# internal_env_board_with_LCD.net
KiCad netlist of a schematic drawn in EAGLE
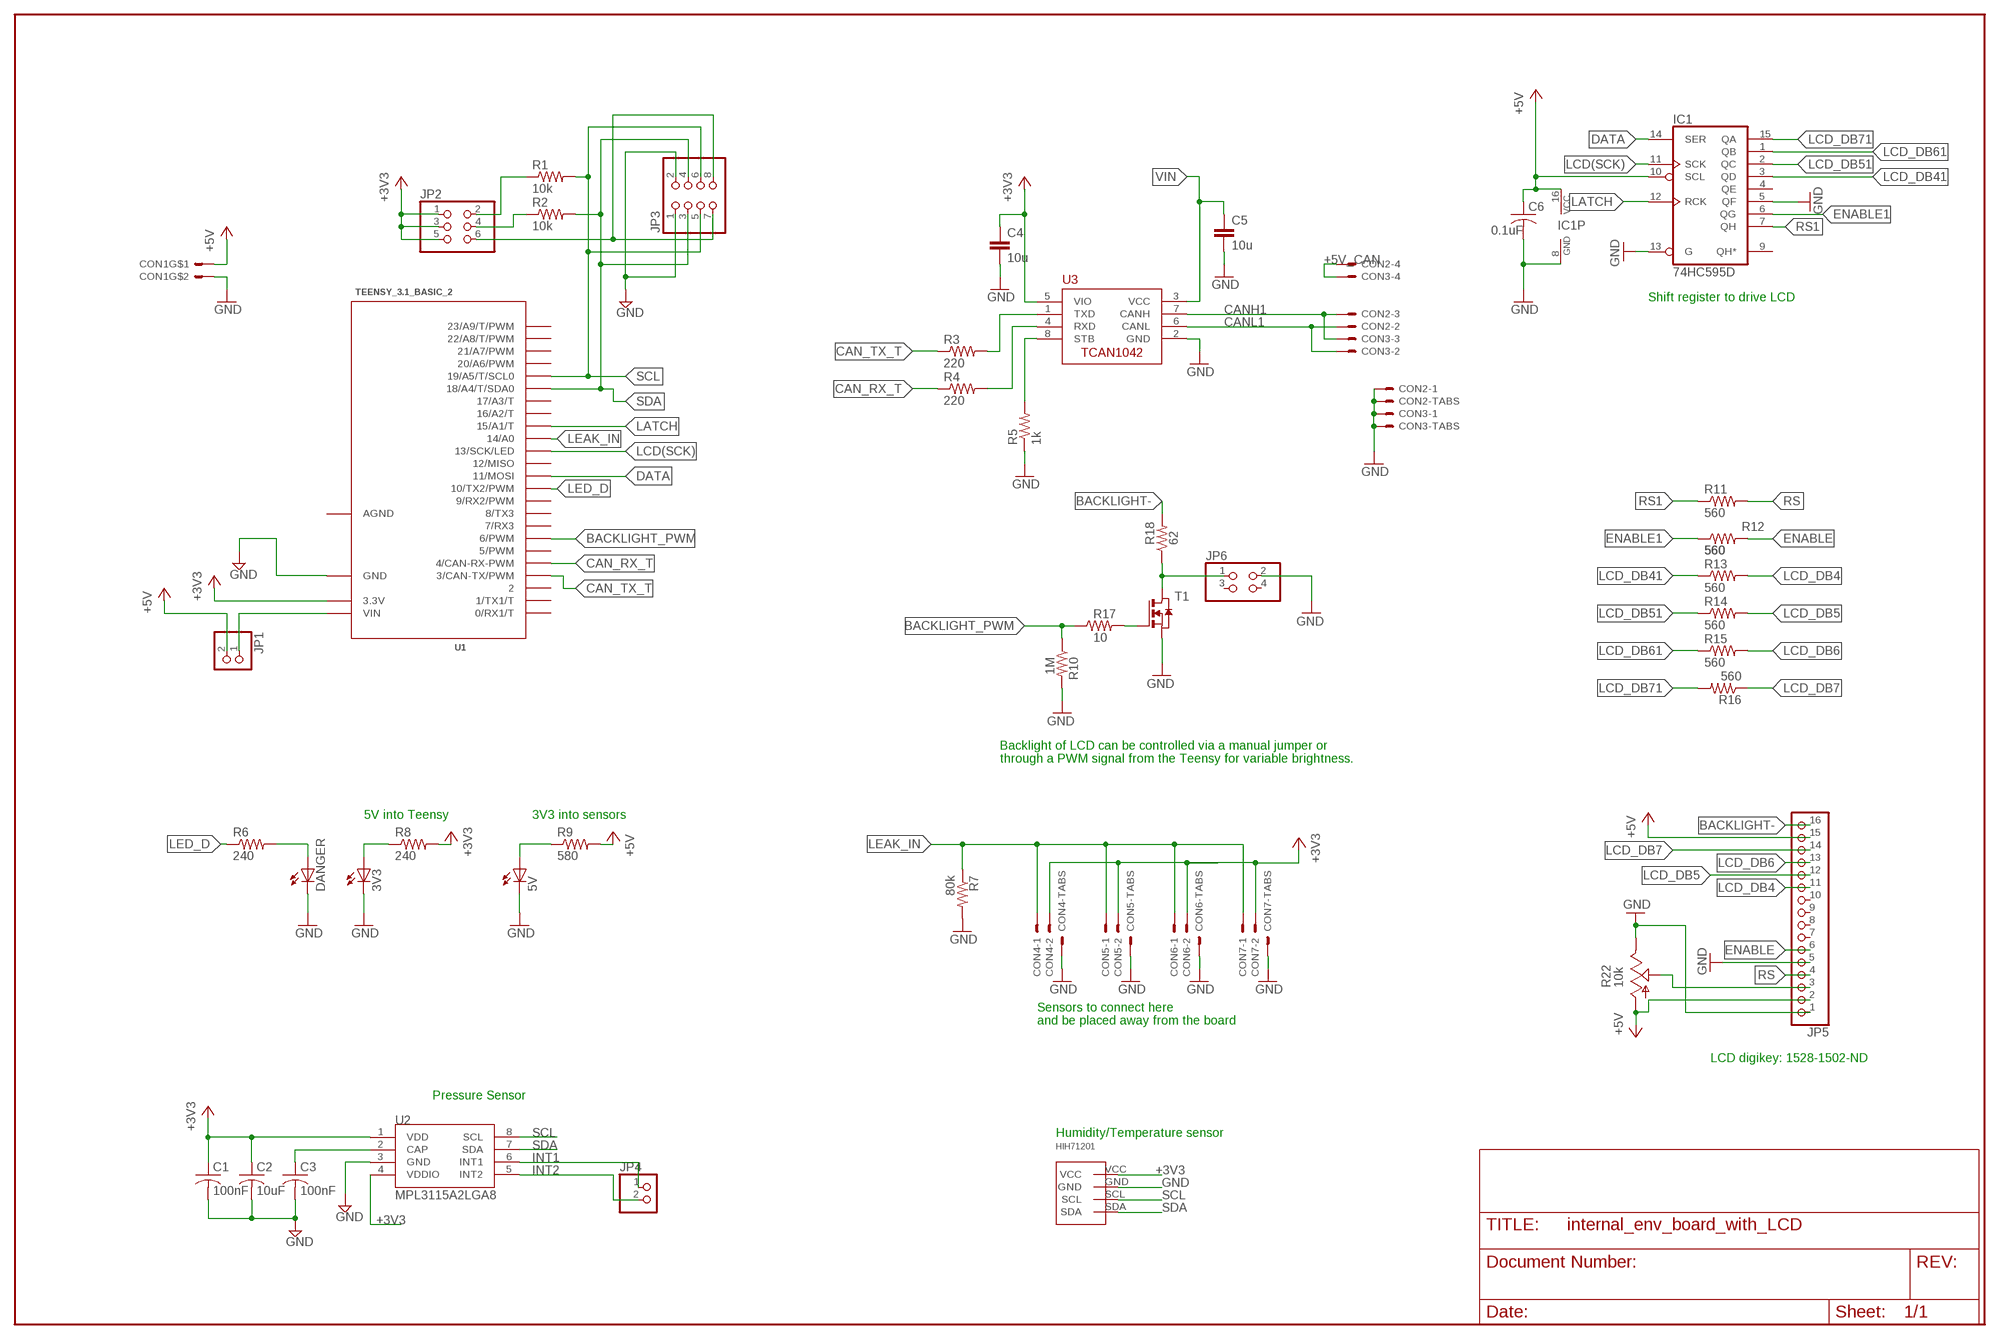
[diagram p0: schematic, sheet 1]

(export (version "E")
  (design (tool "Eeschema 10.0.6"))
  (components
    (comp (ref "3V3")
      (value "LEDSMT1206")
      (footprint "eagle-import:1206")
      (libsource (lib "eagle-import") (part "LEDSMT1206"))
    )
    (comp (ref "5V")
      (value "LEDSMT1206")
      (footprint "eagle-import:1206")
      (libsource (lib "eagle-import") (part "LEDSMT1206"))
    )
    (comp (ref "C1")
      (value "100nF")
      (footprint "eagle-import:C1206")
      (libsource (lib "eagle-import") (part "C-USC1206"))
    )
    (comp (ref "C2")
      (value "10uF")
      (footprint "eagle-import:C1206")
      (libsource (lib "eagle-import") (part "C-USC1206"))
    )
    (comp (ref "C3")
      (value "100nF")
      (footprint "eagle-import:C1206")
      (libsource (lib "eagle-import") (part "C-USC1206"))
    )
    (comp (ref "C4")
      (value "10u")
      (footprint "eagle-import:C0805")
      (libsource (lib "eagle-import") (part "C-EUC0805"))
    )
    (comp (ref "C5")
      (value "10u")
      (footprint "eagle-import:C0805")
      (libsource (lib "eagle-import") (part "C-EUC0805"))
    )
    (comp (ref "C6")
      (value "0.1uF")
      (footprint "eagle-import:C2012")
      (libsource (lib "eagle-import") (part "resistor_C-USC2012"))
    )
    (comp (ref "CON1")
      (value "MOLEX_5566-2")
      (footprint "eagle-import:5566-2")
      (libsource (lib "eagle-import") (part "MOLEX_5566-2"))
    )
    (comp (ref "CON2")
      (value "SM04B-GHS-TB")
      (footprint "eagle-import:SM04B-GHS-TB")
      (libsource (lib "eagle-import") (part "SM04B-GHS-TB"))
    )
    (comp (ref "CON3")
      (value "SM04B-GHS-TB")
      (footprint "eagle-import:SM04B-GHS-TB")
      (libsource (lib "eagle-import") (part "SM04B-GHS-TB"))
    )
    (comp (ref "CON4")
      (value "SM02B-GHS-TB")
      (footprint "eagle-import:SM02B-GHS-TB")
      (libsource (lib "eagle-import") (part "SM02B-GHS-TB"))
    )
    (comp (ref "CON5")
      (value "SM02B-GHS-TB")
      (footprint "eagle-import:SM02B-GHS-TB")
      (libsource (lib "eagle-import") (part "SM02B-GHS-TB"))
    )
    (comp (ref "CON6")
      (value "SM02B-GHS-TB")
      (footprint "eagle-import:SM02B-GHS-TB")
      (libsource (lib "eagle-import") (part "SM02B-GHS-TB"))
    )
    (comp (ref "CON7")
      (value "SM02B-GHS-TB")
      (footprint "eagle-import:SM02B-GHS-TB")
      (libsource (lib "eagle-import") (part "SM02B-GHS-TB"))
    )
    (comp (ref "DANGER")
      (value "LEDSMT1206")
      (footprint "eagle-import:1206")
      (libsource (lib "eagle-import") (part "LEDSMT1206"))
    )
    (comp (ref "HIH71201")
      (value "HIH7120")
      (footprint "eagle-import:SIP4")
      (libsource (lib "eagle-import") (part "HIH7120"))
    )
    (comp (ref "IC1")
      (value "74HC595D")
      (footprint "eagle-import:SO16")
      (libsource (lib "eagle-import") (part "74595DHC"))
    )
    (comp (ref "JP1")
      (value "PINHD-1X2")
      (footprint "eagle-import:1X02")
      (libsource (lib "eagle-import") (part "pinhead_325_PINHD-1X2"))
    )
    (comp (ref "JP2")
      (value "PINHD-2X3")
      (footprint "eagle-import:2X03")
      (libsource (lib "eagle-import") (part "PINHD-2X3"))
    )
    (comp (ref "JP3")
      (value "PINHD-2X4")
      (footprint "eagle-import:2X04")
      (libsource (lib "eagle-import") (part "PINHD-2X4"))
    )
    (comp (ref "JP4")
      (value "PINHD-1X2")
      (footprint "eagle-import:1X02")
      (libsource (lib "eagle-import") (part "PINHD-1X2"))
    )
    (comp (ref "JP5")
      (value "PINHD-1X16")
      (footprint "eagle-import:1X16")
      (libsource (lib "eagle-import") (part "PINHD-1X16"))
    )
    (comp (ref "JP6")
      (value "PINHD-2X2")
      (footprint "eagle-import:2X02")
      (libsource (lib "eagle-import") (part "PINHD-2X2"))
    )
    (comp (ref "R1")
      (value "10k")
      (footprint "eagle-import:R1206")
      (libsource (lib "eagle-import") (part "rcl_334_R-US_R1206"))
    )
    (comp (ref "R2")
      (value "10k")
      (footprint "eagle-import:R1206")
      (libsource (lib "eagle-import") (part "rcl_334_R-US_R1206"))
    )
    (comp (ref "R3")
      (value "220")
      (footprint "eagle-import:R0805")
      (libsource (lib "eagle-import") (part "rcl_334_R-US_R0805"))
    )
    (comp (ref "R4")
      (value "220")
      (footprint "eagle-import:R0805")
      (libsource (lib "eagle-import") (part "rcl_334_R-US_R0805"))
    )
    (comp (ref "R5")
      (value "1k")
      (footprint "eagle-import:R0805")
      (libsource (lib "eagle-import") (part "rcl_334_R-US_R0805"))
    )
    (comp (ref "R6")
      (value "240")
      (footprint "eagle-import:R1206")
      (libsource (lib "eagle-import") (part "resistor_348_R-US_R1206"))
    )
    (comp (ref "R7")
      (value "80k")
      (footprint "eagle-import:R1206")
      (libsource (lib "eagle-import") (part "resistor_348_R-US_R1206"))
    )
    (comp (ref "R8")
      (value "240")
      (footprint "eagle-import:R1206")
      (libsource (lib "eagle-import") (part "resistor_348_R-US_R1206"))
    )
    (comp (ref "R9")
      (value "580")
      (footprint "eagle-import:R1206")
      (libsource (lib "eagle-import") (part "resistor_348_R-US_R1206"))
    )
    (comp (ref "R10")
      (value "1M")
      (footprint "eagle-import:R0805")
      (libsource (lib "eagle-import") (part "rcl_334_R-US_R0805"))
    )
    (comp (ref "R11")
      (value "560")
      (footprint "eagle-import:M2012")
      (libsource (lib "eagle-import") (part "R-US_M2012"))
    )
    (comp (ref "R12")
      (value "560")
      (footprint "eagle-import:M2012")
      (libsource (lib "eagle-import") (part "R-US_M2012"))
    )
    (comp (ref "R13")
      (value "560")
      (footprint "eagle-import:M2012")
      (libsource (lib "eagle-import") (part "R-US_M2012"))
    )
    (comp (ref "R14")
      (value "560")
      (footprint "eagle-import:M2012")
      (libsource (lib "eagle-import") (part "R-US_M2012"))
    )
    (comp (ref "R15")
      (value "560")
      (footprint "eagle-import:M2012")
      (libsource (lib "eagle-import") (part "R-US_M2012"))
    )
    (comp (ref "R16")
      (value "560")
      (footprint "eagle-import:M2012")
      (libsource (lib "eagle-import") (part "R-US_M2012"))
    )
    (comp (ref "R17")
      (value "10")
      (footprint "eagle-import:R0805")
      (libsource (lib "eagle-import") (part "rcl_334_R-US_R0805"))
    )
    (comp (ref "R18")
      (value "62")
      (footprint "eagle-import:R0805")
      (libsource (lib "eagle-import") (part "rcl_334_R-US_R0805"))
    )
    (comp (ref "R22")
      (value "10k")
      (footprint "eagle-import:SM-42_43W")
      (libsource (lib "eagle-import") (part "TRIM_US-SM-42/43W"))
    )
    (comp (ref "T1")
      (value "NMOSSOT23")
      (footprint "eagle-import:SOT-23")
      (libsource (lib "eagle-import") (part "NMOSSOT23"))
    )
    (comp (ref "U1")
      (value "TEENSY_3.1_BASIC_2")
      (footprint "eagle-import:TEENSY_3.1_BASIC_2")
      (libsource (lib "eagle-import") (part "TEENSY_3.1_BASIC_2"))
    )
    (comp (ref "U2")
      (value "MPL3115A2LGA8")
      (footprint "eagle-import:LGA8")
      (libsource (lib "eagle-import") (part "MPL3115A2LGA8"))
    )
    (comp (ref "U3")
      (value "TCAN1042HVDR")
      (footprint "eagle-import:SO-8")
      (libsource (lib "eagle-import") (part "TCAN1042HVDR"))
    )
  )
  (nets
    (net (code "1") (name "+3V3") (class "Default")
      (node (ref "C1") (pin "1") (pinfunction "1_1") (pintype "passive"))
      (node (ref "C2") (pin "1") (pinfunction "1_1") (pintype "passive"))
      (node (ref "C4") (pin "1") (pinfunction "1_1") (pintype "passive"))
      (node (ref "CON4") (pin "P$2") (pinfunction "S_P$2") (pintype "passive"))
      (node (ref "CON5") (pin "P$2") (pinfunction "S_P$2") (pintype "passive"))
      (node (ref "CON6") (pin "P$2") (pinfunction "S_P$2") (pintype "passive"))
      (node (ref "CON7") (pin "P$2") (pinfunction "S_P$2") (pintype "passive"))
      (node (ref "HIH71201") (pin "VCC") (pinfunction "VCC_VCC") (pintype "power_in"))
      (node (ref "JP2") (pin "1") (pinfunction "1_1") (pintype "passive"))
      (node (ref "JP2") (pin "3") (pinfunction "3_3") (pintype "passive"))
      (node (ref "JP2") (pin "5") (pinfunction "5_5") (pintype "passive"))
      (node (ref "R8") (pin "2") (pinfunction "2_2") (pintype "passive"))
      (node (ref "U1") (pin "3.3V") (pinfunction "3.3V_3.3V") (pintype "power_in"))
      (node (ref "U2") (pin "1") (pinfunction "VDD_1") (pintype "bidirectional"))
      (node (ref "U2") (pin "4") (pinfunction "VDDIO_4") (pintype "bidirectional"))
      (node (ref "U3") (pin "5") (pinfunction "VIO_5") (pintype "bidirectional"))
    )
    (net (code "2") (name "+5V") (class "Default")
      (node (ref "C6") (pin "1") (pinfunction "1_1") (pintype "passive"))
      (node (ref "CON1") (pin "1") (pinfunction "S_1") (pintype "passive"))
      (node (ref "IC1") (pin "10") (pinfunction "SCL_10") (pintype "input"))
      (node (ref "IC1") (pin "16") (pinfunction "VCC_16") (pintype "power_in"))
      (node (ref "JP1") (pin "2") (pinfunction "2_2") (pintype "passive"))
      (node (ref "JP5") (pin "15") (pinfunction "15_15") (pintype "passive"))
      (node (ref "JP5") (pin "2") (pinfunction "2_2") (pintype "passive"))
      (node (ref "R22") (pin "1") (pinfunction "A_1") (pintype "passive"))
      (node (ref "R9") (pin "2") (pinfunction "2_2") (pintype "passive"))
    )
    (net (code "3") (name "/+5V_CAN") (class "Default")
      (node (ref "CON2") (pin "P$4") (pinfunction "S_P$4") (pintype "passive"))
      (node (ref "CON3") (pin "P$4") (pinfunction "S_P$4") (pintype "passive"))
    )
    (net (code "4") (name "/AGND") (class "Default")
      (node (ref "U1") (pin "AGND") (pinfunction "AGND_AGND") (pintype "power_in"))
    )
    (net (code "5") (name "/CANH1") (class "Default")
      (node (ref "CON2") (pin "P$3") (pinfunction "S_P$3") (pintype "passive"))
      (node (ref "CON3") (pin "P$3") (pinfunction "S_P$3") (pintype "passive"))
      (node (ref "U3") (pin "7") (pinfunction "CANH_7") (pintype "bidirectional"))
    )
    (net (code "6") (name "/CANL1") (class "Default")
      (node (ref "CON2") (pin "P$2") (pinfunction "S_P$2") (pintype "passive"))
      (node (ref "CON3") (pin "P$2") (pinfunction "S_P$2") (pintype "passive"))
      (node (ref "U3") (pin "6") (pinfunction "CANL_6") (pintype "bidirectional"))
    )
    (net (code "7") (name "/INT1") (class "Default")
      (node (ref "JP4") (pin "1") (pinfunction "1_1") (pintype "passive"))
      (node (ref "U2") (pin "6") (pinfunction "INT1_6") (pintype "bidirectional"))
    )
    (net (code "8") (name "/INT2") (class "Default")
      (node (ref "JP4") (pin "2") (pinfunction "2_2") (pintype "passive"))
      (node (ref "U2") (pin "5") (pinfunction "INT2_5") (pintype "bidirectional"))
    )
    (net (code "9") (name "BACKLIGHT-") (class "Default")
      (node (ref "JP5") (pin "16") (pinfunction "16_16") (pintype "passive"))
      (node (ref "R18") (pin "2") (pinfunction "2_2") (pintype "passive"))
    )
    (net (code "10") (name "BACKLIGHT_PWM") (class "Default")
      (node (ref "R10") (pin "1") (pinfunction "1_1") (pintype "passive"))
      (node (ref "R17") (pin "1") (pinfunction "1_1") (pintype "passive"))
      (node (ref "U1") (pin "6") (pinfunction "6/PWM_6") (pintype "bidirectional"))
    )
    (net (code "11") (name "CAN_RX_T") (class "Default")
      (node (ref "R4") (pin "1") (pinfunction "1_1") (pintype "passive"))
      (node (ref "U1") (pin "4") (pinfunction "4/CAN-RX-PWM_4") (pintype "bidirectional"))
    )
    (net (code "12") (name "CAN_TX_T") (class "Default")
      (node (ref "R3") (pin "1") (pinfunction "1_1") (pintype "passive"))
      (node (ref "U1") (pin "3") (pinfunction "3/CAN-TX/PWM_3") (pintype "bidirectional"))
    )
    (net (code "13") (name "DATA") (class "Default")
      (node (ref "IC1") (pin "14") (pinfunction "SER_14") (pintype "input"))
      (node (ref "U1") (pin "11") (pinfunction "11/MOSI_11") (pintype "bidirectional"))
    )
    (net (code "14") (name "ENABLE") (class "Default")
      (node (ref "JP5") (pin "6") (pinfunction "6_6") (pintype "passive"))
      (node (ref "R12") (pin "2") (pinfunction "2_2") (pintype "passive"))
    )
    (net (code "15") (name "ENABLE1") (class "Default")
      (node (ref "IC1") (pin "6") (pinfunction "QG_6") (pintype "tri_state"))
      (node (ref "R12") (pin "1") (pinfunction "1_1") (pintype "passive"))
    )
    (net (code "16") (name "GND") (class "Default")
      (node (ref "3V3") (pin "C") (pinfunction "C_C") (pintype "passive"))
      (node (ref "5V") (pin "C") (pinfunction "C_C") (pintype "passive"))
      (node (ref "C1") (pin "2") (pinfunction "2_2") (pintype "passive"))
      (node (ref "C2") (pin "2") (pinfunction "2_2") (pintype "passive"))
      (node (ref "C3") (pin "2") (pinfunction "2_2") (pintype "passive"))
      (node (ref "C4") (pin "2") (pinfunction "2_2") (pintype "passive"))
      (node (ref "C5") (pin "2") (pinfunction "2_2") (pintype "passive"))
      (node (ref "C6") (pin "2") (pinfunction "2_2") (pintype "passive"))
      (node (ref "CON1") (pin "2") (pinfunction "S_2") (pintype "passive"))
      (node (ref "CON2") (pin "P$1") (pinfunction "S_P$1") (pintype "passive"))
      (node (ref "CON2") (pin "P$5") (pinfunction "S_P$5") (pintype "passive"))
      (node (ref "CON2") (pin "P$6") (pinfunction "S_P$6") (pintype "passive"))
      (node (ref "CON3") (pin "P$1") (pinfunction "S_P$1") (pintype "passive"))
      (node (ref "CON3") (pin "P$5") (pinfunction "S_P$5") (pintype "passive"))
      (node (ref "CON3") (pin "P$6") (pinfunction "S_P$6") (pintype "passive"))
      (node (ref "CON4") (pin "P$3") (pinfunction "S_P$3") (pintype "passive"))
      (node (ref "CON4") (pin "P$4") (pinfunction "S_P$4") (pintype "passive"))
      (node (ref "CON5") (pin "P$3") (pinfunction "S_P$3") (pintype "passive"))
      (node (ref "CON5") (pin "P$4") (pinfunction "S_P$4") (pintype "passive"))
      (node (ref "CON6") (pin "P$3") (pinfunction "S_P$3") (pintype "passive"))
      (node (ref "CON6") (pin "P$4") (pinfunction "S_P$4") (pintype "passive"))
      (node (ref "CON7") (pin "P$3") (pinfunction "S_P$3") (pintype "passive"))
      (node (ref "CON7") (pin "P$4") (pinfunction "S_P$4") (pintype "passive"))
      (node (ref "DANGER") (pin "C") (pinfunction "C_C") (pintype "passive"))
      (node (ref "HIH71201") (pin "GND") (pinfunction "GND_GND") (pintype "power_in"))
      (node (ref "IC1") (pin "13") (pinfunction "G_13") (pintype "input"))
      (node (ref "IC1") (pin "5") (pinfunction "QF_5") (pintype "tri_state"))
      (node (ref "IC1") (pin "8") (pinfunction "GND_8") (pintype "power_in"))
      (node (ref "JP3") (pin "1") (pinfunction "1_1") (pintype "passive"))
      (node (ref "JP3") (pin "2") (pinfunction "2_2") (pintype "passive"))
      (node (ref "JP5") (pin "1") (pinfunction "1_1") (pintype "passive"))
      (node (ref "JP5") (pin "5") (pinfunction "5_5") (pintype "passive"))
      (node (ref "JP6") (pin "2") (pinfunction "2_2") (pintype "passive"))
      (node (ref "R10") (pin "2") (pinfunction "2_2") (pintype "passive"))
      (node (ref "R22") (pin "3") (pinfunction "E_3") (pintype "passive"))
      (node (ref "R5") (pin "1") (pinfunction "1_1") (pintype "passive"))
      (node (ref "R7") (pin "2") (pinfunction "2_2") (pintype "passive"))
      (node (ref "T1") (pin "2") (pinfunction "S_2") (pintype "passive"))
      (node (ref "U1") (pin "GND") (pinfunction "GND_GND") (pintype "power_in"))
      (node (ref "U2") (pin "3") (pinfunction "GND_3") (pintype "bidirectional"))
      (node (ref "U3") (pin "2") (pinfunction "GND_2") (pintype "bidirectional"))
    )
    (net (code "17") (name "LATCH") (class "Default")
      (node (ref "IC1") (pin "12") (pinfunction "RCK_12") (pintype "input"))
      (node (ref "U1") (pin "15/A1") (pinfunction "15/A1/T_15/A1") (pintype "bidirectional"))
    )
    (net (code "18") (name "LCD(SCK)") (class "Default")
      (node (ref "IC1") (pin "11") (pinfunction "SCK_11") (pintype "input"))
      (node (ref "U1") (pin "13") (pinfunction "13/SCK/LED_13") (pintype "bidirectional"))
    )
    (net (code "19") (name "LCD_DB4") (class "Default")
      (node (ref "JP5") (pin "11") (pinfunction "11_11") (pintype "passive"))
      (node (ref "R13") (pin "2") (pinfunction "2_2") (pintype "passive"))
    )
    (net (code "20") (name "LCD_DB5") (class "Default")
      (node (ref "JP5") (pin "12") (pinfunction "12_12") (pintype "passive"))
      (node (ref "R14") (pin "2") (pinfunction "2_2") (pintype "passive"))
    )
    (net (code "21") (name "LCD_DB6") (class "Default")
      (node (ref "JP5") (pin "13") (pinfunction "13_13") (pintype "passive"))
      (node (ref "R15") (pin "2") (pinfunction "2_2") (pintype "passive"))
    )
    (net (code "22") (name "LCD_DB7") (class "Default")
      (node (ref "JP5") (pin "14") (pinfunction "14_14") (pintype "passive"))
      (node (ref "R16") (pin "1") (pinfunction "1_1") (pintype "passive"))
    )
    (net (code "23") (name "LCD_DB41") (class "Default")
      (node (ref "IC1") (pin "3") (pinfunction "QD_3") (pintype "tri_state"))
      (node (ref "R13") (pin "1") (pinfunction "1_1") (pintype "passive"))
    )
    (net (code "24") (name "LCD_DB51") (class "Default")
      (node (ref "IC1") (pin "2") (pinfunction "QC_2") (pintype "tri_state"))
      (node (ref "R14") (pin "1") (pinfunction "1_1") (pintype "passive"))
    )
    (net (code "25") (name "LCD_DB61") (class "Default")
      (node (ref "IC1") (pin "1") (pinfunction "QB_1") (pintype "tri_state"))
      (node (ref "R15") (pin "1") (pinfunction "1_1") (pintype "passive"))
    )
    (net (code "26") (name "LCD_DB71") (class "Default")
      (node (ref "IC1") (pin "15") (pinfunction "QA_15") (pintype "tri_state"))
      (node (ref "R16") (pin "2") (pinfunction "2_2") (pintype "passive"))
    )
    (net (code "27") (name "LEAK_IN") (class "Default")
      (node (ref "CON4") (pin "P$1") (pinfunction "S_P$1") (pintype "passive"))
      (node (ref "CON5") (pin "P$1") (pinfunction "S_P$1") (pintype "passive"))
      (node (ref "CON6") (pin "P$1") (pinfunction "S_P$1") (pintype "passive"))
      (node (ref "CON7") (pin "P$1") (pinfunction "S_P$1") (pintype "passive"))
      (node (ref "R7") (pin "1") (pinfunction "1_1") (pintype "passive"))
      (node (ref "U1") (pin "14/A0") (pinfunction "14/A0_14/A0") (pintype "bidirectional"))
    )
    (net (code "28") (name "LED_D") (class "Default")
      (node (ref "R6") (pin "1") (pinfunction "1_1") (pintype "passive"))
      (node (ref "U1") (pin "10") (pinfunction "10/TX2/PWM_10") (pintype "bidirectional"))
    )
    (net (code "29") (name "Net-(3V3-PadA)") (class "Default")
      (node (ref "3V3") (pin "A") (pinfunction "A_A") (pintype "passive"))
      (node (ref "R8") (pin "1") (pinfunction "1_1") (pintype "passive"))
    )
    (net (code "30") (name "Net-(5V-PadA)") (class "Default")
      (node (ref "5V") (pin "A") (pinfunction "A_A") (pintype "passive"))
      (node (ref "R9") (pin "1") (pinfunction "1_1") (pintype "passive"))
    )
    (net (code "31") (name "Net-(DANGER-PadA)") (class "Default")
      (node (ref "DANGER") (pin "A") (pinfunction "A_A") (pintype "passive"))
      (node (ref "R6") (pin "2") (pinfunction "2_2") (pintype "passive"))
    )
    (net (code "32") (name "Net-(JP2-Pad2)") (class "Default")
      (node (ref "JP2") (pin "2") (pinfunction "2_2") (pintype "passive"))
      (node (ref "R1") (pin "1") (pinfunction "1_1") (pintype "passive"))
    )
    (net (code "33") (name "Net-(JP2-Pad4)") (class "Default")
      (node (ref "JP2") (pin "4") (pinfunction "4_4") (pintype "passive"))
      (node (ref "R2") (pin "1") (pinfunction "1_1") (pintype "passive"))
    )
    (net (code "34") (name "Net-(JP2-Pad6)") (class "Default")
      (node (ref "JP2") (pin "6") (pinfunction "6_6") (pintype "passive"))
      (node (ref "JP3") (pin "7") (pinfunction "7_7") (pintype "passive"))
      (node (ref "JP3") (pin "8") (pinfunction "8_8") (pintype "passive"))
    )
    (net (code "35") (name "Net-(R22-S)") (class "Default")
      (node (ref "JP5") (pin "3") (pinfunction "3_3") (pintype "passive"))
      (node (ref "R22") (pin "2") (pinfunction "S_2") (pintype "passive"))
    )
    (net (code "36") (name "Net-(T1-D)") (class "Default")
      (node (ref "JP6") (pin "1") (pinfunction "1_1") (pintype "passive"))
      (node (ref "R18") (pin "1") (pinfunction "1_1") (pintype "passive"))
      (node (ref "T1") (pin "1") (pinfunction "D_1") (pintype "passive"))
    )
    (net (code "37") (name "Net-(T1-G)") (class "Default")
      (node (ref "R17") (pin "2") (pinfunction "2_2") (pintype "passive"))
      (node (ref "T1") (pin "3") (pinfunction "G_3") (pintype "passive"))
    )
    (net (code "38") (name "Net-(U2-CAP)") (class "Default")
      (node (ref "C3") (pin "1") (pinfunction "1_1") (pintype "passive"))
      (node (ref "U2") (pin "2") (pinfunction "CAP_2") (pintype "bidirectional"))
    )
    (net (code "39") (name "Net-(U3-RXD)") (class "Default")
      (node (ref "R4") (pin "2") (pinfunction "2_2") (pintype "passive"))
      (node (ref "U3") (pin "4") (pinfunction "RXD_4") (pintype "bidirectional"))
    )
    (net (code "40") (name "Net-(U3-STB)") (class "Default")
      (node (ref "R5") (pin "2") (pinfunction "2_2") (pintype "passive"))
      (node (ref "U3") (pin "8") (pinfunction "STB_8") (pintype "bidirectional"))
    )
    (net (code "41") (name "Net-(U3-TXD)") (class "Default")
      (node (ref "R3") (pin "2") (pinfunction "2_2") (pintype "passive"))
      (node (ref "U3") (pin "1") (pinfunction "TXD_1") (pintype "bidirectional"))
    )
    (net (code "42") (name "RS") (class "Default")
      (node (ref "JP5") (pin "4") (pinfunction "4_4") (pintype "passive"))
      (node (ref "R11") (pin "2") (pinfunction "2_2") (pintype "passive"))
    )
    (net (code "43") (name "RS1") (class "Default")
      (node (ref "IC1") (pin "7") (pinfunction "QH_7") (pintype "tri_state"))
      (node (ref "R11") (pin "1") (pinfunction "1_1") (pintype "passive"))
    )
    (net (code "44") (name "SCL") (class "Default")
      (node (ref "HIH71201") (pin "SCL") (pinfunction "SCL_SCL") (pintype "bidirectional"))
      (node (ref "JP3") (pin "5") (pinfunction "5_5") (pintype "passive"))
      (node (ref "JP3") (pin "6") (pinfunction "6_6") (pintype "passive"))
      (node (ref "R1") (pin "2") (pinfunction "2_2") (pintype "passive"))
      (node (ref "U1") (pin "19/A5") (pinfunction "19/A5/T/SCL0_19/A5") (pintype "bidirectional"))
      (node (ref "U2") (pin "8") (pinfunction "SCL_8") (pintype "bidirectional"))
    )
    (net (code "45") (name "SDA") (class "Default")
      (node (ref "HIH71201") (pin "SDA") (pinfunction "SDA_SDA") (pintype "bidirectional"))
      (node (ref "JP3") (pin "3") (pinfunction "3_3") (pintype "passive"))
      (node (ref "JP3") (pin "4") (pinfunction "4_4") (pintype "passive"))
      (node (ref "R2") (pin "2") (pinfunction "2_2") (pintype "passive"))
      (node (ref "U1") (pin "18/A4") (pinfunction "18/A4/T/SDA0_18/A4") (pintype "bidirectional"))
      (node (ref "U2") (pin "7") (pinfunction "SDA_7") (pintype "bidirectional"))
    )
    (net (code "46") (name "VIN") (class "Default")
      (node (ref "C5") (pin "1") (pinfunction "1_1") (pintype "passive"))
      (node (ref "JP1") (pin "1") (pinfunction "1_1") (pintype "passive"))
      (node (ref "U1") (pin "VIN") (pinfunction "VIN_VIN") (pintype "power_in"))
      (node (ref "U3") (pin "3") (pinfunction "VCC_3") (pintype "bidirectional"))
    )
    (net (code "47") (name "unconnected-(IC1A-QE-Pad4)") (class "Default")
      (node (ref "IC1") (pin "4") (pinfunction "QE_4") (pintype "tri_state"))
    )
    (net (code "48") (name "unconnected-(IC1A-QH*-Pad9)") (class "Default")
      (node (ref "IC1") (pin "9") (pinfunction "QH*_9") (pintype "tri_state"))
    )
    (net (code "49") (name "unconnected-(JP5-Pad7)") (class "Default")
      (node (ref "JP5") (pin "7") (pinfunction "7_7") (pintype "passive"))
    )
    (net (code "50") (name "unconnected-(JP5-Pad8)") (class "Default")
      (node (ref "JP5") (pin "8") (pinfunction "8_8") (pintype "passive"))
    )
    (net (code "51") (name "unconnected-(JP5-Pad9)") (class "Default")
      (node (ref "JP5") (pin "9") (pinfunction "9_9") (pintype "passive"))
    )
    (net (code "52") (name "unconnected-(JP5-Pad10)") (class "Default")
      (node (ref "JP5") (pin "10") (pinfunction "10_10") (pintype "passive"))
    )
    (net (code "53") (name "unconnected-(JP6-Pad3)") (class "Default")
      (node (ref "JP6") (pin "3") (pinfunction "3_3") (pintype "passive"))
    )
    (net (code "54") (name "unconnected-(JP6-Pad4)") (class "Default")
      (node (ref "JP6") (pin "4") (pinfunction "4_4") (pintype "passive"))
    )
    (net (code "55") (name "unconnected-(U1-0{slash}RX1{slash}T-Pad0)") (class "Default")
      (node (ref "U1") (pin "0") (pinfunction "0/RX1/T_0") (pintype "bidirectional"))
    )
    (net (code "56") (name "unconnected-(U1-1{slash}TX1{slash}T-Pad1)") (class "Default")
      (node (ref "U1") (pin "1") (pinfunction "1/TX1/T_1") (pintype "bidirectional"))
    )
    (net (code "57") (name "unconnected-(U1-5{slash}PWM-Pad5)") (class "Default")
      (node (ref "U1") (pin "5") (pinfunction "5/PWM_5") (pintype "bidirectional"))
    )
    (net (code "58") (name "unconnected-(U1-7{slash}RX3-Pad7)") (class "Default")
      (node (ref "U1") (pin "7") (pinfunction "7/RX3_7") (pintype "bidirectional"))
    )
    (net (code "59") (name "unconnected-(U1-8{slash}TX3-Pad8)") (class "Default")
      (node (ref "U1") (pin "8") (pinfunction "8/TX3_8") (pintype "bidirectional"))
    )
    (net (code "60") (name "unconnected-(U1-9{slash}RX2{slash}PWM-Pad9)") (class "Default")
      (node (ref "U1") (pin "9") (pinfunction "9/RX2/PWM_9") (pintype "bidirectional"))
    )
    (net (code "61") (name "unconnected-(U1-12{slash}MISO-Pad12)") (class "Default")
      (node (ref "U1") (pin "12") (pinfunction "12/MISO_12") (pintype "bidirectional"))
    )
    (net (code "62") (name "unconnected-(U1-16{slash}A2{slash}T-Pad16{slash}A2)") (class "Default")
      (node (ref "U1") (pin "16/A2") (pinfunction "16/A2/T_16/A2") (pintype "bidirectional"))
    )
    (net (code "63") (name "unconnected-(U1-17{slash}A3{slash}T-Pad17{slash}A3)") (class "Default")
      (node (ref "U1") (pin "17/A3") (pinfunction "17/A3/T_17/A3") (pintype "bidirectional"))
    )
    (net (code "64") (name "unconnected-(U1-20{slash}A6{slash}PWM-Pad20{slash}A6)") (class "Default")
      (node (ref "U1") (pin "20/A6") (pinfunction "20/A6/PWM_20/A6") (pintype "bidirectional"))
    )
    (net (code "65") (name "unconnected-(U1-21{slash}A7{slash}PWM-Pad21{slash}A7)") (class "Default")
      (node (ref "U1") (pin "21/A7") (pinfunction "21/A7/PWM_21/A7") (pintype "bidirectional"))
    )
    (net (code "66") (name "unconnected-(U1-22{slash}A8{slash}T{slash}PWM-Pad22{slash}A8)") (class "Default")
      (node (ref "U1") (pin "22/A8") (pinfunction "22/A8/T/PWM_22/A8") (pintype "bidirectional"))
    )
    (net (code "67") (name "unconnected-(U1-23{slash}A9{slash}T{slash}PWM-Pad23{slash}A9)") (class "Default")
      (node (ref "U1") (pin "23/A9") (pinfunction "23/A9/T/PWM_23/A9") (pintype "bidirectional"))
    )
    (net (code "68") (name "unconnected-(U1-Pad2)") (class "Default")
      (node (ref "U1") (pin "2") (pinfunction "2_2") (pintype "bidirectional"))
    )
  )
)
